# schmittTrigger.net
KiCad netlist of a schematic drawn in EAGLE
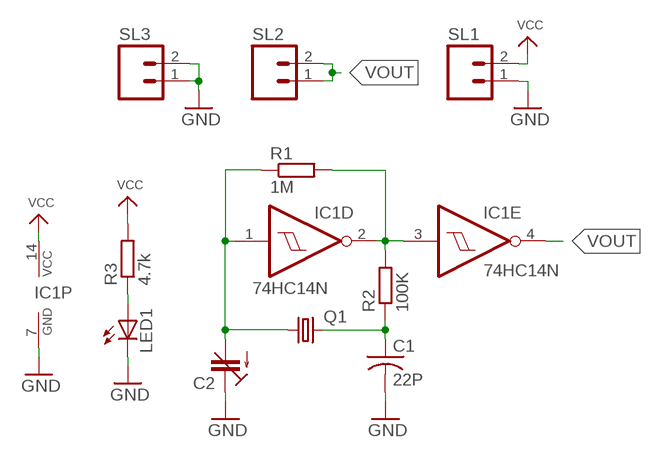
[diagram p0: schematic, sheet 1]

(export (version "E")
  (design (tool "Eeschema 10.0.6"))
  (components
    (comp (ref "C1")
      (value "22P")
      (footprint "eagle-import:C025-024X044")
      (libsource (lib "eagle-import") (part "C-US025-024X044"))
    )
    (comp (ref "C2")
      (value "C-TRIMM808")
      (footprint "eagle-import:CTRIM808-BC")
      (libsource (lib "eagle-import") (part "C-TRIMM808"))
    )
    (comp (ref "IC1")
      (value "74HC14N")
      (footprint "eagle-import:DIL14")
      (libsource (lib "eagle-import") (part "7414NHC"))
    )
    (comp (ref "LED1")
      (value "LED3MM")
      (footprint "eagle-import:LED3MM")
      (libsource (lib "eagle-import") (part "LED3MM"))
    )
    (comp (ref "Q1")
      (value "CRYSTALTC26H")
      (footprint "eagle-import:TC26H")
      (libsource (lib "eagle-import") (part "CRYSTALTC26H"))
    )
    (comp (ref "R1")
      (value "1M")
      (footprint "eagle-import:0204_5")
      (libsource (lib "eagle-import") (part "R-EU_0204/5"))
    )
    (comp (ref "R2")
      (value "100K")
      (footprint "eagle-import:0204_5")
      (libsource (lib "eagle-import") (part "R-EU_0204/5"))
    )
    (comp (ref "R3")
      (value "4.7k")
      (footprint "eagle-import:0204_5")
      (libsource (lib "eagle-import") (part "R-EU_0204/5"))
    )
    (comp (ref "SL1")
      (value "M02")
      (footprint "eagle-import:02P")
      (libsource (lib "eagle-import") (part "M02"))
    )
    (comp (ref "SL2")
      (value "M02")
      (footprint "eagle-import:02P")
      (libsource (lib "eagle-import") (part "M02"))
    )
    (comp (ref "SL3")
      (value "M02")
      (footprint "eagle-import:02P")
      (libsource (lib "eagle-import") (part "M02"))
    )
  )
  (nets
    (net (code "1") (name "GND") (class "Default")
      (node (ref "C1") (pin "2") (pinfunction "2_2") (pintype "passive"))
      (node (ref "C2") (pin "1") (pinfunction "E_1") (pintype "passive"))
      (node (ref "IC1") (pin "7") (pinfunction "GND_7") (pintype "power_in"))
      (node (ref "LED1") (pin "K") (pinfunction "C_K") (pintype "passive"))
      (node (ref "SL1") (pin "1") (pinfunction "1_1") (pintype "passive"))
      (node (ref "SL3") (pin "1") (pinfunction "1_1") (pintype "passive"))
      (node (ref "SL3") (pin "2") (pinfunction "2_2") (pintype "passive"))
    )
    (net (code "2") (name "Net-(C1-Pad1)") (class "Default")
      (node (ref "C1") (pin "1") (pinfunction "1_1") (pintype "passive"))
      (node (ref "Q1") (pin "2") (pinfunction "2_2") (pintype "passive"))
      (node (ref "R2") (pin "1") (pinfunction "1_1") (pintype "passive"))
    )
    (net (code "3") (name "Net-(C2-A)") (class "Default")
      (node (ref "C2") (pin "2") (pinfunction "A_2") (pintype "passive"))
      (node (ref "IC1") (pin "1") (pinfunction "I_1") (pintype "input"))
      (node (ref "Q1") (pin "1") (pinfunction "1_1") (pintype "passive"))
      (node (ref "R1") (pin "1") (pinfunction "1_1") (pintype "passive"))
    )
    (net (code "4") (name "Net-(IC1D-O)") (class "Default")
      (node (ref "IC1") (pin "2") (pinfunction "O_2") (pintype "output"))
      (node (ref "IC1") (pin "3") (pinfunction "I_3") (pintype "input"))
      (node (ref "R1") (pin "2") (pinfunction "2_2") (pintype "passive"))
      (node (ref "R2") (pin "2") (pinfunction "2_2") (pintype "passive"))
    )
    (net (code "5") (name "Net-(LED1-PadA)") (class "Default")
      (node (ref "LED1") (pin "A") (pinfunction "A_A") (pintype "passive"))
      (node (ref "R3") (pin "1") (pinfunction "1_1") (pintype "passive"))
    )
    (net (code "6") (name "VCC") (class "Default")
      (node (ref "IC1") (pin "14") (pinfunction "VCC_14") (pintype "power_in"))
      (node (ref "R3") (pin "2") (pinfunction "2_2") (pintype "passive"))
      (node (ref "SL1") (pin "2") (pinfunction "2_2") (pintype "passive"))
    )
    (net (code "7") (name "VOUT") (class "Default")
      (node (ref "IC1") (pin "4") (pinfunction "O_4") (pintype "output"))
      (node (ref "SL2") (pin "1") (pinfunction "1_1") (pintype "passive"))
      (node (ref "SL2") (pin "2") (pinfunction "2_2") (pintype "passive"))
    )
  )
)
